# IR_sensor.net
KiCad netlist of a schematic drawn in EAGLE
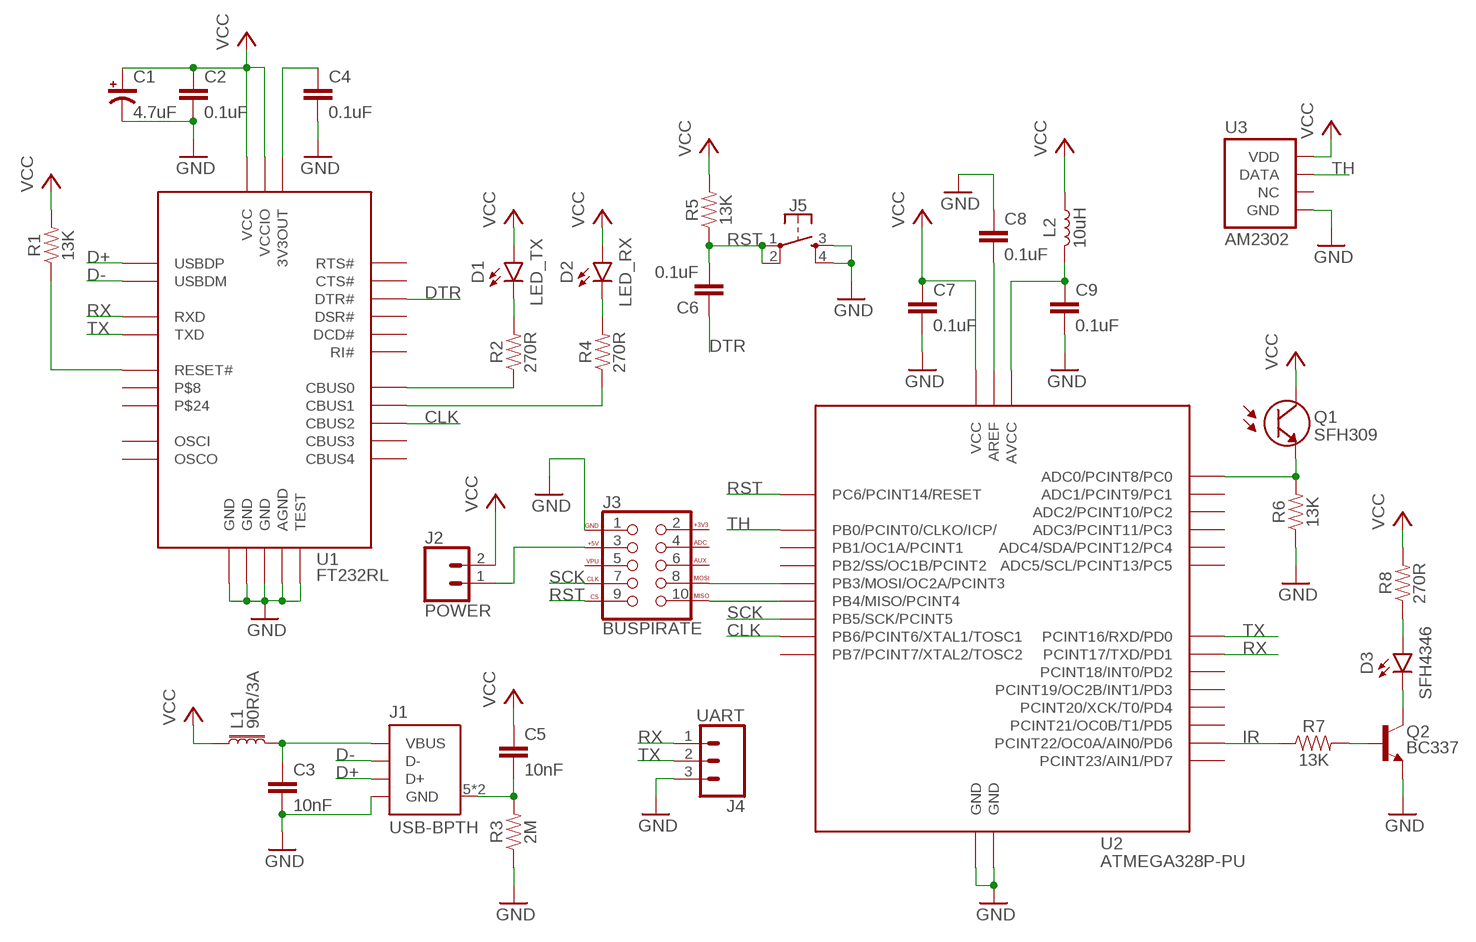
[diagram p0: schematic, sheet 1]

(export (version "E")
  (design (tool "Eeschema 10.0.6"))
  (components
    (comp (ref "C1")
      (value "4.7uF")
      (footprint "eagle-import:CPOL-RADIAL-2.5MM-5MM")
      (libsource (lib "eagle-import") (part "CAP-POL"))
    )
    (comp (ref "C2")
      (value "0.1uF")
      (footprint "eagle-import:CAP-PTH-5MM")
      (libsource (lib "eagle-import") (part "CAPPTH-5MM"))
    )
    (comp (ref "C3")
      (value "10nF")
      (footprint "eagle-import:CAP-PTH-2.5MM")
      (libsource (lib "eagle-import") (part "CAPPTH2.5MM"))
    )
    (comp (ref "C4")
      (value "0.1uF")
      (footprint "eagle-import:CAP-PTH-5MM")
      (libsource (lib "eagle-import") (part "CAPPTH-5MM"))
    )
    (comp (ref "C5")
      (value "10nF")
      (footprint "eagle-import:CAP-PTH-5MM")
      (libsource (lib "eagle-import") (part "CAPPTH-5MM"))
    )
    (comp (ref "C6")
      (value "0.1uF")
      (footprint "eagle-import:CAP-PTH-5MM")
      (libsource (lib "eagle-import") (part "CAPPTH-5MM"))
    )
    (comp (ref "C7")
      (value "0.1uF")
      (footprint "eagle-import:CAP-PTH-5MM")
      (libsource (lib "eagle-import") (part "CAPPTH-5MM"))
    )
    (comp (ref "C8")
      (value "0.1uF")
      (footprint "eagle-import:CAP-PTH-5MM")
      (libsource (lib "eagle-import") (part "CAPPTH-5MM"))
    )
    (comp (ref "C9")
      (value "0.1uF")
      (footprint "eagle-import:CAP-PTH-5MM")
      (libsource (lib "eagle-import") (part "CAPPTH-5MM"))
    )
    (comp (ref "D1")
      (value "LED_TX")
      (footprint "eagle-import:LED_5MM")
      (libsource (lib "eagle-import") (part "LEDPTH-5MM"))
    )
    (comp (ref "D2")
      (value "LED_RX")
      (footprint "eagle-import:LED_5MM")
      (libsource (lib "eagle-import") (part "LEDPTH-5MM"))
    )
    (comp (ref "D3")
      (value "SFH4346")
      (footprint "eagle-import:LED_3MM_R")
      (libsource (lib "eagle-import") (part "LEDR-3MM"))
    )
    (comp (ref "J1")
      (value "USB-BPTH")
      (footprint "eagle-import:USB-B-PTH")
      (libsource (lib "eagle-import") (part "USB-BPTH"))
    )
    (comp (ref "J2")
      (value "POWER")
      (footprint "eagle-import:1X02")
      (libsource (lib "eagle-import") (part "CONN_02"))
    )
    (comp (ref "J3")
      (value "BUSPIRATE")
      (footprint "eagle-import:2X5-SHROUDED")
      (libsource (lib "eagle-import") (part "ICSPPTH"))
    )
    (comp (ref "J4")
      (value "UART")
      (footprint "eagle-import:1X03")
      (libsource (lib "eagle-import") (part "CONN_03"))
    )
    (comp (ref "J5")
      (value "SWITCH")
      (footprint "eagle-import:TACTILE_SWITCH_PTH_6.0MM")
      (libsource (lib "eagle-import") (part "SWITCH"))
    )
    (comp (ref "L1")
      (value "90R/3A")
      (footprint "eagle-import:AXIAL-0.3")
      (libsource (lib "eagle-import") (part "FERRITE_BEADPTH"))
    )
    (comp (ref "L2")
      (value "10uH")
      (footprint "eagle-import:AXIAL-0.4")
      (libsource (lib "eagle-import") (part "INDUCTORPTH"))
    )
    (comp (ref "Q1")
      (value "SFH309")
      (footprint "eagle-import:LED_3MM_R")
      (libsource (lib "eagle-import") (part "PHOTOTRANSISTORPTH-R"))
    )
    (comp (ref "Q2")
      (value "BC337")
      (footprint "eagle-import:TO-92")
      (libsource (lib "eagle-import") (part "NPNPTH"))
    )
    (comp (ref "R1")
      (value "13K")
      (footprint "eagle-import:AXIAL-0.3")
      (libsource (lib "eagle-import") (part "RESISTORPTH"))
    )
    (comp (ref "R2")
      (value "270R")
      (footprint "eagle-import:AXIAL-0.3")
      (libsource (lib "eagle-import") (part "RESISTORPTH"))
    )
    (comp (ref "R3")
      (value "2M")
      (footprint "eagle-import:AXIAL-0.3")
      (libsource (lib "eagle-import") (part "RESISTORPTH"))
    )
    (comp (ref "R4")
      (value "270R")
      (footprint "eagle-import:AXIAL-0.3")
      (libsource (lib "eagle-import") (part "RESISTORPTH"))
    )
    (comp (ref "R5")
      (value "13K")
      (footprint "eagle-import:AXIAL-0.3")
      (libsource (lib "eagle-import") (part "RESISTORPTH"))
    )
    (comp (ref "R6")
      (value "13K")
      (footprint "eagle-import:AXIAL-0.3")
      (libsource (lib "eagle-import") (part "RESISTORPTH"))
    )
    (comp (ref "R7")
      (value "13K")
      (footprint "eagle-import:AXIAL-0.3")
      (libsource (lib "eagle-import") (part "RESISTORPTH"))
    )
    (comp (ref "R8")
      (value "270R")
      (footprint "eagle-import:AXIAL-0.3")
      (libsource (lib "eagle-import") (part "RESISTORPTH"))
    )
    (comp (ref "U1")
      (value "FT232RL")
      (footprint "eagle-import:TSSOP-28-BL")
      (libsource (lib "eagle-import") (part "FT232RL"))
    )
    (comp (ref "U2")
      (value "ATMEGA328P-PU")
      (footprint "eagle-import:DIP28")
      (libsource (lib "eagle-import") (part "ATMEGA328P-PU"))
    )
    (comp (ref "U3")
      (value "AM2302")
      (footprint "eagle-import:SNR4-2.54")
      (libsource (lib "eagle-import") (part "AM2302"))
    )
  )
  (nets
    (net (code "1") (name "/+3V3") (class "Default")
      (node (ref "J3") (pin "2") (pinfunction "+3V3_2") (pintype "power_in"))
    )
    (net (code "2") (name "/CLK") (class "Default")
      (node (ref "U1") (pin "13") (pinfunction "CBUS2_13") (pintype "bidirectional"))
      (node (ref "U2") (pin "9") (pinfunction "PB6/PCINT6/XTAL1/TOSC1_9") (pintype "bidirectional"))
    )
    (net (code "3") (name "/D+") (class "Default")
      (node (ref "J1") (pin "3") (pinfunction "D+_3") (pintype "bidirectional"))
      (node (ref "U1") (pin "15") (pinfunction "USBDP_15") (pintype "bidirectional"))
    )
    (net (code "4") (name "/D-") (class "Default")
      (node (ref "J1") (pin "2") (pinfunction "D-_2") (pintype "bidirectional"))
      (node (ref "U1") (pin "16") (pinfunction "USBDM_16") (pintype "bidirectional"))
    )
    (net (code "5") (name "/DTR") (class "Default")
      (node (ref "C6") (pin "1") (pinfunction "1_1") (pintype "passive"))
      (node (ref "U1") (pin "2") (pinfunction "DTR#_2") (pintype "output"))
    )
    (net (code "6") (name "/IR") (class "Default")
      (node (ref "R7") (pin "P$1") (pinfunction "1_P$1") (pintype "passive"))
      (node (ref "U2") (pin "12") (pinfunction "PCINT22/OC0A/AIN0/PD6_12") (pintype "bidirectional"))
    )
    (net (code "7") (name "/RST") (class "Default")
      (node (ref "C6") (pin "2") (pinfunction "2_2") (pintype "passive"))
      (node (ref "J3") (pin "9") (pinfunction "CS_9") (pintype "passive"))
      (node (ref "J5") (pin "1") (pinfunction "1_1") (pintype "passive"))
      (node (ref "J5") (pin "2") (pinfunction "2_2") (pintype "passive"))
      (node (ref "R5") (pin "P$1") (pinfunction "1_P$1") (pintype "passive"))
      (node (ref "U2") (pin "1") (pinfunction "PC6/PCINT14/RESET_1") (pintype "bidirectional"))
    )
    (net (code "8") (name "/RX") (class "Default")
      (node (ref "J4") (pin "1") (pinfunction "1_1") (pintype "passive"))
      (node (ref "U1") (pin "5") (pinfunction "RXD_5") (pintype "input"))
      (node (ref "U2") (pin "3") (pinfunction "PCINT17/TXD/PD1_3") (pintype "bidirectional"))
    )
    (net (code "9") (name "/SCK") (class "Default")
      (node (ref "J3") (pin "7") (pinfunction "CLK_7") (pintype "passive"))
      (node (ref "U2") (pin "19") (pinfunction "PB5/SCK/PCINT5_19") (pintype "bidirectional"))
    )
    (net (code "10") (name "/TH") (class "Default")
      (node (ref "U2") (pin "14") (pinfunction "PB0/PCINT0/CLKO/ICP/_14") (pintype "bidirectional"))
      (node (ref "U3") (pin "P$2") (pinfunction "DATA_P$2") (pintype "bidirectional"))
    )
    (net (code "11") (name "/TX") (class "Default")
      (node (ref "J4") (pin "2") (pinfunction "2_2") (pintype "passive"))
      (node (ref "U1") (pin "1") (pinfunction "TXD_1") (pintype "output"))
      (node (ref "U2") (pin "2") (pinfunction "PCINT16/RXD/PD0_2") (pintype "bidirectional"))
    )
    (net (code "12") (name "GND") (class "Default")
      (node (ref "C1") (pin "2") (pinfunction "-_2") (pintype "passive"))
      (node (ref "C2") (pin "2") (pinfunction "2_2") (pintype "passive"))
      (node (ref "C3") (pin "2") (pinfunction "2_2") (pintype "passive"))
      (node (ref "C4") (pin "2") (pinfunction "2_2") (pintype "passive"))
      (node (ref "C7") (pin "2") (pinfunction "2_2") (pintype "passive"))
      (node (ref "C8") (pin "1") (pinfunction "1_1") (pintype "passive"))
      (node (ref "C9") (pin "2") (pinfunction "2_2") (pintype "passive"))
      (node (ref "J1") (pin "4") (pinfunction "GND_4") (pintype "power_in"))
      (node (ref "J3") (pin "1") (pinfunction "GND_1") (pintype "power_in"))
      (node (ref "J4") (pin "3") (pinfunction "3_3") (pintype "passive"))
      (node (ref "J5") (pin "3") (pinfunction "3_3") (pintype "passive"))
      (node (ref "J5") (pin "4") (pinfunction "4_4") (pintype "passive"))
      (node (ref "Q2") (pin "1") (pinfunction "E_1") (pintype "passive"))
      (node (ref "R3") (pin "P$1") (pinfunction "1_P$1") (pintype "passive"))
      (node (ref "R6") (pin "P$1") (pinfunction "1_P$1") (pintype "passive"))
      (node (ref "U1") (pin "18") (pinfunction "GND_18") (pintype "power_in"))
      (node (ref "U1") (pin "21") (pinfunction "GND_21") (pintype "power_in"))
      (node (ref "U1") (pin "25") (pinfunction "AGND_25") (pintype "power_in"))
      (node (ref "U1") (pin "26") (pinfunction "TEST_26") (pintype "input"))
      (node (ref "U1") (pin "7") (pinfunction "GND_7") (pintype "power_in"))
      (node (ref "U2") (pin "22") (pinfunction "GND_22") (pintype "power_in"))
      (node (ref "U2") (pin "8") (pinfunction "GND_8") (pintype "power_in"))
      (node (ref "U3") (pin "P$4") (pinfunction "GND_P$4") (pintype "power_in"))
    )
    (net (code "13") (name "Net-(J1-VBUS)") (class "Default")
      (node (ref "C3") (pin "1") (pinfunction "1_1") (pintype "passive"))
      (node (ref "J1") (pin "1") (pinfunction "VBUS_1") (pintype "power_in"))
      (node (ref "L1") (pin "P$2") (pinfunction "2_P$2") (pintype "passive"))
    )
    (net (code "14") (name "Net-(J3-+5V)") (class "Default")
      (node (ref "J2") (pin "1") (pinfunction "1_1") (pintype "passive"))
      (node (ref "J3") (pin "3") (pinfunction "+5V_3") (pintype "power_in"))
    )
    (net (code "15") (name "Net-(J3-MISO)") (class "Default")
      (node (ref "J3") (pin "10") (pinfunction "MISO_10") (pintype "passive"))
      (node (ref "U2") (pin "18") (pinfunction "PB4/MISO/PCINT4_18") (pintype "bidirectional"))
    )
    (net (code "16") (name "Net-(J3-MOSI)") (class "Default")
      (node (ref "J3") (pin "8") (pinfunction "MOSI_8") (pintype "passive"))
      (node (ref "U2") (pin "17") (pinfunction "PB3/MOSI/OC2A/PCINT3_17") (pintype "bidirectional"))
    )
    (net (code "17") (name "Net-(L2-2)") (class "Default")
      (node (ref "C9") (pin "1") (pinfunction "1_1") (pintype "passive"))
      (node (ref "L2") (pin "P$2") (pinfunction "2_P$2") (pintype "passive"))
      (node (ref "U2") (pin "20") (pinfunction "AVCC_20") (pintype "power_in"))
    )
    (net (code "18") (name "Net-(Q1-E)") (class "Default")
      (node (ref "Q1") (pin "A") (pinfunction "E_A") (pintype "passive"))
      (node (ref "R6") (pin "P$2") (pinfunction "2_P$2") (pintype "passive"))
      (node (ref "U2") (pin "23") (pinfunction "ADC0/PCINT8/PC0_23") (pintype "bidirectional"))
    )
    (net (code "19") (name "Net-(Q2-B)") (class "Default")
      (node (ref "Q2") (pin "2") (pinfunction "B_2") (pintype "passive"))
      (node (ref "R7") (pin "P$2") (pinfunction "2_P$2") (pintype "passive"))
    )
    (net (code "20") (name "Net-(Q2-C)") (class "Default")
      (node (ref "D3") (pin "K") (pinfunction "K_K") (pintype "passive"))
      (node (ref "Q2") (pin "3") (pinfunction "C_3") (pintype "passive"))
    )
    (net (code "21") (name "Net-(R1-1)") (class "Default")
      (node (ref "R1") (pin "P$1") (pinfunction "1_P$1") (pintype "passive"))
      (node (ref "U1") (pin "19") (pinfunction "RESET#_19") (pintype "input"))
    )
    (net (code "22") (name "Net-(R2-1)") (class "Default")
      (node (ref "R2") (pin "P$1") (pinfunction "1_P$1") (pintype "passive"))
      (node (ref "U1") (pin "23") (pinfunction "CBUS0_23") (pintype "bidirectional"))
    )
    (net (code "23") (name "Net-(R2-2)") (class "Default")
      (node (ref "D1") (pin "K") (pinfunction "K_K") (pintype "passive"))
      (node (ref "R2") (pin "P$2") (pinfunction "2_P$2") (pintype "passive"))
    )
    (net (code "24") (name "Net-(R3-2)") (class "Default")
      (node (ref "C5") (pin "2") (pinfunction "2_2") (pintype "passive"))
      (node (ref "J1") (pin "5") (pinfunction "SHIELD_5") (pintype "passive"))
      (node (ref "J1") (pin "6") (pinfunction "SHIELD_6") (pintype "passive"))
      (node (ref "R3") (pin "P$2") (pinfunction "2_P$2") (pintype "passive"))
    )
    (net (code "25") (name "Net-(R4-1)") (class "Default")
      (node (ref "R4") (pin "P$1") (pinfunction "1_P$1") (pintype "passive"))
      (node (ref "U1") (pin "22") (pinfunction "CBUS1_22") (pintype "bidirectional"))
    )
    (net (code "26") (name "Net-(R4-2)") (class "Default")
      (node (ref "D2") (pin "K") (pinfunction "K_K") (pintype "passive"))
      (node (ref "R4") (pin "P$2") (pinfunction "2_P$2") (pintype "passive"))
    )
    (net (code "27") (name "Net-(R8-1)") (class "Default")
      (node (ref "D3") (pin "A") (pinfunction "A_A") (pintype "passive"))
      (node (ref "R8") (pin "P$1") (pinfunction "1_P$1") (pintype "passive"))
    )
    (net (code "28") (name "Net-(U1-3V3OUT)") (class "Default")
      (node (ref "C4") (pin "1") (pinfunction "1_1") (pintype "passive"))
      (node (ref "U1") (pin "17") (pinfunction "3V3OUT_17") (pintype "output"))
    )
    (net (code "29") (name "Net-(U2-AREF)") (class "Default")
      (node (ref "C8") (pin "2") (pinfunction "2_2") (pintype "passive"))
      (node (ref "U2") (pin "21") (pinfunction "AREF_21") (pintype "power_in"))
    )
    (net (code "30") (name "VCC") (class "Default")
      (node (ref "C1") (pin "1") (pinfunction "+_1") (pintype "passive"))
      (node (ref "C2") (pin "1") (pinfunction "1_1") (pintype "passive"))
      (node (ref "C5") (pin "1") (pinfunction "1_1") (pintype "passive"))
      (node (ref "C7") (pin "1") (pinfunction "1_1") (pintype "passive"))
      (node (ref "D1") (pin "A") (pinfunction "A_A") (pintype "passive"))
      (node (ref "D2") (pin "A") (pinfunction "A_A") (pintype "passive"))
      (node (ref "J2") (pin "2") (pinfunction "2_2") (pintype "passive"))
      (node (ref "L1") (pin "P$1") (pinfunction "1_P$1") (pintype "passive"))
      (node (ref "L2") (pin "P$1") (pinfunction "1_P$1") (pintype "passive"))
      (node (ref "Q1") (pin "K") (pinfunction "C_K") (pintype "passive"))
      (node (ref "R1") (pin "P$2") (pinfunction "2_P$2") (pintype "passive"))
      (node (ref "R5") (pin "P$2") (pinfunction "2_P$2") (pintype "passive"))
      (node (ref "R8") (pin "P$2") (pinfunction "2_P$2") (pintype "passive"))
      (node (ref "U1") (pin "20") (pinfunction "VCC_20") (pintype "power_in"))
      (node (ref "U1") (pin "4") (pinfunction "VCCIO_4") (pintype "power_in"))
      (node (ref "U2") (pin "7") (pinfunction "VCC_7") (pintype "power_in"))
      (node (ref "U3") (pin "P$1") (pinfunction "VDD_P$1") (pintype "power_in"))
    )
    (net (code "31") (name "unconnected-(J3-ADC-Pad4)") (class "Default")
      (node (ref "J3") (pin "4") (pinfunction "ADC_4") (pintype "passive"))
    )
    (net (code "32") (name "unconnected-(J3-AUX-Pad6)") (class "Default")
      (node (ref "J3") (pin "6") (pinfunction "AUX_6") (pintype "passive"))
    )
    (net (code "33") (name "unconnected-(J3-VPU-Pad5)") (class "Default")
      (node (ref "J3") (pin "5") (pinfunction "VPU_5") (pintype "passive"))
    )
    (net (code "34") (name "unconnected-(U1-CBUS3-Pad14)") (class "Default")
      (node (ref "U1") (pin "14") (pinfunction "CBUS3_14") (pintype "bidirectional"))
    )
    (net (code "35") (name "unconnected-(U1-CBUS4-Pad12)") (class "Default")
      (node (ref "U1") (pin "12") (pinfunction "CBUS4_12") (pintype "bidirectional"))
    )
    (net (code "36") (name "unconnected-(U1-CTS#-Pad11)") (class "Default")
      (node (ref "U1") (pin "11") (pinfunction "CTS#_11") (pintype "input"))
    )
    (net (code "37") (name "unconnected-(U1-DCD#-Pad10)") (class "Default")
      (node (ref "U1") (pin "10") (pinfunction "DCD#_10") (pintype "input"))
    )
    (net (code "38") (name "unconnected-(U1-DSR#-Pad9)") (class "Default")
      (node (ref "U1") (pin "9") (pinfunction "DSR#_9") (pintype "input"))
    )
    (net (code "39") (name "unconnected-(U1-OSCI-Pad27)") (class "Default")
      (node (ref "U1") (pin "27") (pinfunction "OSCI_27") (pintype "input"))
    )
    (net (code "40") (name "unconnected-(U1-OSCO-Pad28)") (class "Default")
      (node (ref "U1") (pin "28") (pinfunction "OSCO_28") (pintype "output"))
    )
    (net (code "41") (name "unconnected-(U1-P$8-Pad8)") (class "Default")
      (node (ref "U1") (pin "8") (pinfunction "P$8_8") (pintype "no_connect"))
    )
    (net (code "42") (name "unconnected-(U1-P$24-Pad24)") (class "Default")
      (node (ref "U1") (pin "24") (pinfunction "P$24_24") (pintype "no_connect"))
    )
    (net (code "43") (name "unconnected-(U1-RI#-Pad6)") (class "Default")
      (node (ref "U1") (pin "6") (pinfunction "RI#_6") (pintype "input"))
    )
    (net (code "44") (name "unconnected-(U1-RTS#-Pad3)") (class "Default")
      (node (ref "U1") (pin "3") (pinfunction "RTS#_3") (pintype "output"))
    )
    (net (code "45") (name "unconnected-(U2-ADC1{slash}PCINT9{slash}PC1-Pad24)") (class "Default")
      (node (ref "U2") (pin "24") (pinfunction "ADC1/PCINT9/PC1_24") (pintype "bidirectional"))
    )
    (net (code "46") (name "unconnected-(U2-ADC2{slash}PCINT10{slash}PC2-Pad25)") (class "Default")
      (node (ref "U2") (pin "25") (pinfunction "ADC2/PCINT10/PC2_25") (pintype "bidirectional"))
    )
    (net (code "47") (name "unconnected-(U2-ADC3{slash}PCINT11{slash}PC3-Pad26)") (class "Default")
      (node (ref "U2") (pin "26") (pinfunction "ADC3/PCINT11/PC3_26") (pintype "bidirectional"))
    )
    (net (code "48") (name "unconnected-(U2-ADC4{slash}SDA{slash}PCINT12{slash}PC4-Pad27)") (class "Default")
      (node (ref "U2") (pin "27") (pinfunction "ADC4/SDA/PCINT12/PC4_27") (pintype "bidirectional"))
    )
    (net (code "49") (name "unconnected-(U2-ADC5{slash}SCL{slash}PCINT13{slash}PC5-Pad28)") (class "Default")
      (node (ref "U2") (pin "28") (pinfunction "ADC5/SCL/PCINT13/PC5_28") (pintype "bidirectional"))
    )
    (net (code "50") (name "unconnected-(U2-PB1{slash}OC1A{slash}PCINT1-Pad15)") (class "Default")
      (node (ref "U2") (pin "15") (pinfunction "PB1/OC1A/PCINT1_15") (pintype "bidirectional"))
    )
    (net (code "51") (name "unconnected-(U2-PB2{slash}SS{slash}OC1B{slash}PCINT2-Pad16)") (class "Default")
      (node (ref "U2") (pin "16") (pinfunction "PB2/SS/OC1B/PCINT2_16") (pintype "bidirectional"))
    )
    (net (code "52") (name "unconnected-(U2-PB7{slash}PCINT7{slash}XTAL2{slash}TOSC2-Pad10)") (class "Default")
      (node (ref "U2") (pin "10") (pinfunction "PB7/PCINT7/XTAL2/TOSC2_10") (pintype "bidirectional"))
    )
    (net (code "53") (name "unconnected-(U2-PCINT18{slash}INT0{slash}PD2-Pad4)") (class "Default")
      (node (ref "U2") (pin "4") (pinfunction "PCINT18/INT0/PD2_4") (pintype "bidirectional"))
    )
    (net (code "54") (name "unconnected-(U2-PCINT19{slash}OC2B{slash}INT1{slash}PD3-Pad5)") (class "Default")
      (node (ref "U2") (pin "5") (pinfunction "PCINT19/OC2B/INT1/PD3_5") (pintype "bidirectional"))
    )
    (net (code "55") (name "unconnected-(U2-PCINT20{slash}XCK{slash}T0{slash}PD4-Pad6)") (class "Default")
      (node (ref "U2") (pin "6") (pinfunction "PCINT20/XCK/T0/PD4_6") (pintype "bidirectional"))
    )
    (net (code "56") (name "unconnected-(U2-PCINT21{slash}OC0B{slash}T1{slash}PD5-Pad11)") (class "Default")
      (node (ref "U2") (pin "11") (pinfunction "PCINT21/OC0B/T1/PD5_11") (pintype "bidirectional"))
    )
    (net (code "57") (name "unconnected-(U2-PCINT23{slash}AIN1{slash}PD7-Pad13)") (class "Default")
      (node (ref "U2") (pin "13") (pinfunction "PCINT23/AIN1/PD7_13") (pintype "bidirectional"))
    )
    (net (code "58") (name "unconnected-(U3-NC-PadP$3)") (class "Default")
      (node (ref "U3") (pin "P$3") (pinfunction "NC_P$3") (pintype "no_connect"))
    )
  )
)
